# magicmouth-v0_1-ds.net
KiCad netlist of a schematic drawn in EAGLE
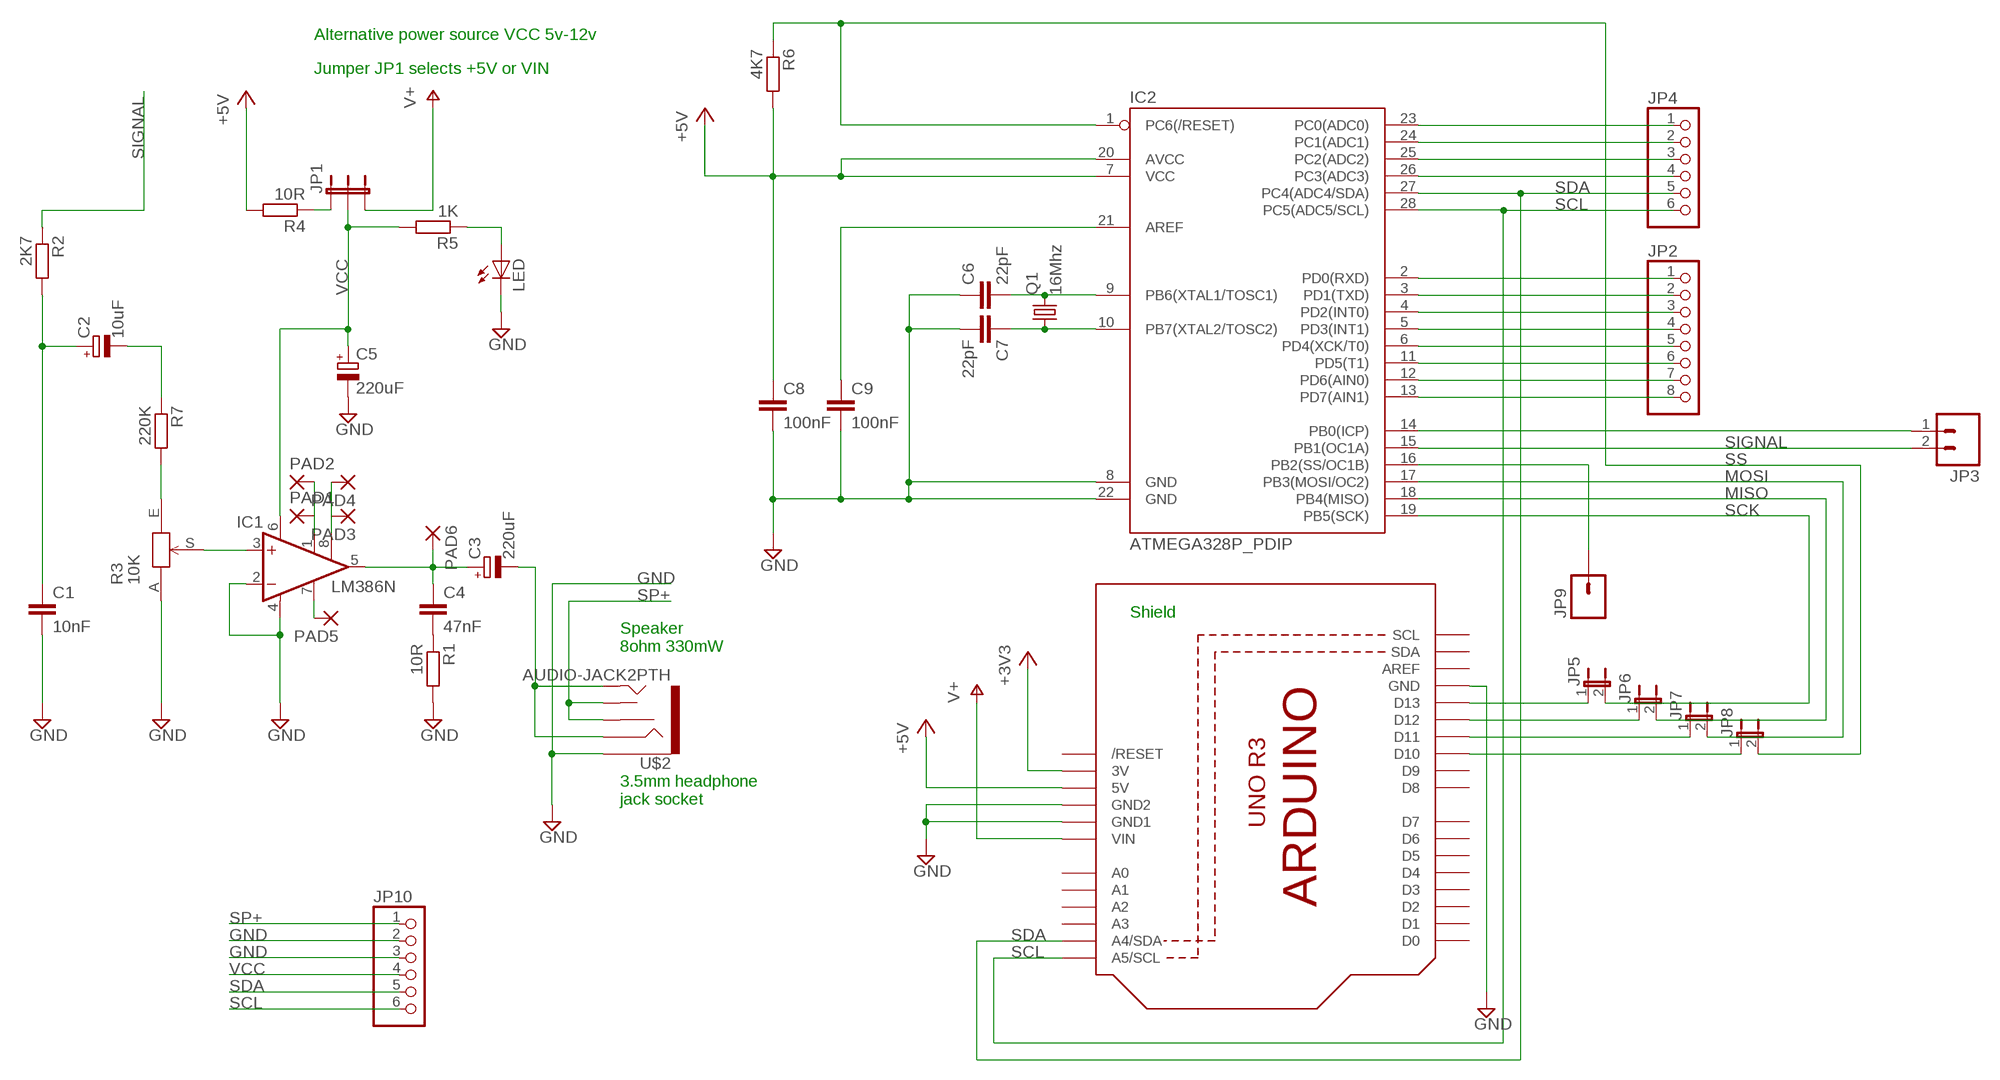
[diagram p0: schematic, sheet 1]

(export (version "E")
  (design (tool "Eeschema 10.0.6"))
  (components
    (comp (ref "C1")
      (value "10nF")
      (footprint "eagle-import:C050-025X075")
      (libsource (lib "eagle-import") (part "C-EU050-025X075"))
    )
    (comp (ref "C2")
      (value "10uF")
      (footprint "eagle-import:E2,5-7")
      (libsource (lib "eagle-import") (part "CPOL-EUE2.5-7"))
    )
    (comp (ref "C3")
      (value "220uF")
      (footprint "eagle-import:TT2D7")
      (libsource (lib "eagle-import") (part "CPOL-EUTT2D7"))
    )
    (comp (ref "C4")
      (value "47nF")
      (footprint "eagle-import:C050-025X075")
      (libsource (lib "eagle-import") (part "C-EU050-025X075"))
    )
    (comp (ref "C5")
      (value "220uF")
      (footprint "eagle-import:TT2D7")
      (libsource (lib "eagle-import") (part "CPOL-EUTT2D7"))
    )
    (comp (ref "C6")
      (value "22pF")
      (footprint "eagle-import:C025-025X050")
      (fields (field (name "CAPACITANCE") "22 pf"))
      (libsource (lib "eagle-import") (part "C-EU025-025X050"))
    )
    (comp (ref "C7")
      (value "22pF")
      (footprint "eagle-import:C025-025X050")
      (fields (field (name "CAPACITANCE") "22 pf"))
      (libsource (lib "eagle-import") (part "C-EU025-025X050"))
    )
    (comp (ref "C8")
      (value "100nF")
      (footprint "eagle-import:C025-025X050")
      (fields (field (name "CAPACITANCE") "10 nF"))
      (libsource (lib "eagle-import") (part "C-EU025-025X050"))
    )
    (comp (ref "C9")
      (value "100nF")
      (footprint "eagle-import:C025-025X050")
      (fields (field (name "CAPACITANCE") "100 nF"))
      (libsource (lib "eagle-import") (part "C-EU025-025X050"))
    )
    (comp (ref "IC1")
      (value "LM386N")
      (footprint "eagle-import:DIL08")
      (libsource (lib "eagle-import") (part "LM386?-N1"))
    )
    (comp (ref "IC2")
      (value "ATMEGA328P_PDIP")
      (footprint "eagle-import:DIL28-3")
      (libsource (lib "eagle-import") (part "ATMEGA328P_PDIP"))
    )
    (comp (ref "JP1")
      (value "JUMPER-3PTH")
      (footprint "eagle-import:1X03")
      (libsource (lib "eagle-import") (part "JUMPER-3PTH"))
    )
    (comp (ref "JP2")
      (value "PINHD-1X8CLEANBIG")
      (footprint "eagle-import:1X08-CLEANBIG")
      (libsource (lib "eagle-import") (part "PINHD-1X8CLEANBIG"))
    )
    (comp (ref "JP3")
      (value "M021X02_NO_SILK")
      (footprint "eagle-import:1X02_NO_SILK")
      (libsource (lib "eagle-import") (part "M021X02_NO_SILK"))
    )
    (comp (ref "JP4")
      (value "PINHD-1X6CB")
      (footprint "eagle-import:1X06-CLEANBIG")
      (libsource (lib "eagle-import") (part "PINHD-1X6CB"))
    )
    (comp (ref "JP5")
      (value "JUMPER-2PTH")
      (footprint "eagle-import:1X02")
      (libsource (lib "eagle-import") (part "JUMPER-2PTH"))
    )
    (comp (ref "JP6")
      (value "JUMPER-2PTH")
      (footprint "eagle-import:1X02")
      (libsource (lib "eagle-import") (part "JUMPER-2PTH"))
    )
    (comp (ref "JP7")
      (value "JUMPER-2PTH")
      (footprint "eagle-import:1X02")
      (libsource (lib "eagle-import") (part "JUMPER-2PTH"))
    )
    (comp (ref "JP8")
      (value "JUMPER-2PTH")
      (footprint "eagle-import:1X02")
      (libsource (lib "eagle-import") (part "JUMPER-2PTH"))
    )
    (comp (ref "JP9")
      (value "M01SMDNS")
      (footprint "eagle-import:1X01NS")
      (libsource (lib "eagle-import") (part "M01SMDNS"))
    )
    (comp (ref "JP10")
      (value "PINHD-1X6CB")
      (footprint "eagle-import:1X06-CLEANBIG")
      (libsource (lib "eagle-import") (part "PINHD-1X6CB"))
    )
    (comp (ref "LED")
      (value "LED3MM")
      (footprint "eagle-import:LED3MM")
      (libsource (lib "eagle-import") (part "LED3MM"))
    )
    (comp (ref "PAD1")
      (value "1,6/0,8")
      (footprint "eagle-import:1,6_0,8")
      (libsource (lib "eagle-import") (part "1,6/0,8"))
    )
    (comp (ref "PAD2")
      (value "1,6/0,8")
      (footprint "eagle-import:1,6_0,8")
      (libsource (lib "eagle-import") (part "1,6/0,8"))
    )
    (comp (ref "PAD3")
      (value "1,6/0,8")
      (footprint "eagle-import:1,6_0,8")
      (libsource (lib "eagle-import") (part "1,6/0,8"))
    )
    (comp (ref "PAD4")
      (value "1,6/0,8")
      (footprint "eagle-import:1,6_0,8")
      (libsource (lib "eagle-import") (part "1,6/0,8"))
    )
    (comp (ref "PAD5")
      (value "1,6/0,8")
      (footprint "eagle-import:1,6_0,8")
      (libsource (lib "eagle-import") (part "1,6/0,8"))
    )
    (comp (ref "PAD6")
      (value "1,6/0,8")
      (footprint "eagle-import:1,6_0,8")
      (libsource (lib "eagle-import") (part "1,6/0,8"))
    )
    (comp (ref "Q1")
      (value "16Mhz")
      (footprint "eagle-import:HC49_S")
      (libsource (lib "eagle-import") (part "CRYSTALHC49S"))
    )
    (comp (ref "R1")
      (value "10R")
      (footprint "eagle-import:0207_7")
      (libsource (lib "eagle-import") (part "resistor_R-EU_0207/7"))
    )
    (comp (ref "R2")
      (value "2K7")
      (footprint "eagle-import:0207_7")
      (libsource (lib "eagle-import") (part "R-EU_0207/7"))
    )
    (comp (ref "R3")
      (value "10K")
      (footprint "eagle-import:3352T")
      (libsource (lib "eagle-import") (part "TPOT3352"))
    )
    (comp (ref "R4")
      (value "10R")
      (footprint "eagle-import:0207_7")
      (libsource (lib "eagle-import") (part "R-EU_0207/7"))
    )
    (comp (ref "R5")
      (value "1K")
      (footprint "eagle-import:0207_7")
      (libsource (lib "eagle-import") (part "R-EU_0207/7"))
    )
    (comp (ref "R6")
      (value "4K7")
      (footprint "eagle-import:0207_7")
      (fields (field (name "RESISTANCE") "4K7"))
      (libsource (lib "eagle-import") (part "R-EU_0207/7"))
    )
    (comp (ref "R7")
      (value "220K")
      (footprint "eagle-import:0207_7")
      (libsource (lib "eagle-import") (part "resistor_R-EU_0207/7"))
    )
    (comp (ref "U$2")
      (value "AUDIO-JACK2PTH")
      (footprint "eagle-import:AUDIO-JACK")
      (libsource (lib "eagle-import") (part "AUDIO-JACK2PTH"))
    )
    (comp (ref "U1")
      (value "ARDUINOR3-NOIOREF-NOTEXT")
      (footprint "eagle-import:ARDUINOR3-NOTEXT-NOIOREF")
      (libsource (lib "eagle-import") (part "ARDUINOR3-NOIOREF-NOTEXT"))
    )
  )
  (nets
    (net (code "1") (name "+3V3") (class "Default")
      (node (ref "U1") (pin "3V") (pinfunction "3V_3V") (pintype "power_in"))
    )
    (net (code "2") (name "+5V") (class "Default")
      (node (ref "C8") (pin "1") (pinfunction "1_1") (pintype "passive"))
      (node (ref "IC2") (pin "20") (pinfunction "AVCC_20") (pintype "bidirectional"))
      (node (ref "IC2") (pin "7") (pinfunction "VCC_7") (pintype "bidirectional"))
      (node (ref "R4") (pin "2") (pinfunction "2_2") (pintype "passive"))
      (node (ref "R6") (pin "2") (pinfunction "2_2") (pintype "passive"))
      (node (ref "U1") (pin "5V") (pinfunction "5V_5V") (pintype "power_in"))
    )
    (net (code "3") (name "/MISO") (class "Default")
      (node (ref "IC2") (pin "18") (pinfunction "PB4(MISO)_18") (pintype "bidirectional"))
      (node (ref "JP6") (pin "2") (pinfunction "2_2") (pintype "passive"))
    )
    (net (code "4") (name "/MOSI") (class "Default")
      (node (ref "IC2") (pin "17") (pinfunction "PB3(MOSI/OC2)_17") (pintype "bidirectional"))
      (node (ref "JP7") (pin "2") (pinfunction "2_2") (pintype "passive"))
    )
    (net (code "5") (name "/SCK") (class "Default")
      (node (ref "IC2") (pin "19") (pinfunction "PB5(SCK)_19") (pintype "bidirectional"))
      (node (ref "JP5") (pin "2") (pinfunction "2_2") (pintype "passive"))
    )
    (net (code "6") (name "/SCL") (class "Default")
      (node (ref "IC2") (pin "28") (pinfunction "PC5(ADC5/SCL)_28") (pintype "bidirectional"))
      (node (ref "JP10") (pin "6") (pinfunction "6_6") (pintype "passive"))
      (node (ref "JP4") (pin "6") (pinfunction "6_6") (pintype "passive"))
      (node (ref "U1") (pin "A5") (pinfunction "A5/SCL_A5") (pintype "bidirectional"))
    )
    (net (code "7") (name "/SDA") (class "Default")
      (node (ref "IC2") (pin "27") (pinfunction "PC4(ADC4/SDA)_27") (pintype "bidirectional"))
      (node (ref "JP10") (pin "5") (pinfunction "5_5") (pintype "passive"))
      (node (ref "JP4") (pin "5") (pinfunction "5_5") (pintype "passive"))
      (node (ref "U1") (pin "A4") (pinfunction "A4/SDA_A4") (pintype "bidirectional"))
    )
    (net (code "8") (name "/SIGNAL") (class "Default")
      (node (ref "IC2") (pin "15") (pinfunction "PB1(OC1A)_15") (pintype "bidirectional"))
      (node (ref "JP3") (pin "2") (pinfunction "2_2") (pintype "passive"))
      (node (ref "R2") (pin "1") (pinfunction "1_1") (pintype "passive"))
    )
    (net (code "9") (name "/SP+") (class "Default")
      (node (ref "JP10") (pin "1") (pinfunction "1_1") (pintype "passive"))
      (node (ref "U$2") (pin "RSH") (pinfunction "RSH_RSH") (pintype "bidirectional"))
      (node (ref "U$2") (pin "TSH") (pinfunction "TSH_TSH") (pintype "bidirectional"))
    )
    (net (code "10") (name "/SS") (class "Default")
      (node (ref "IC2") (pin "1") (pinfunction "PC6(/RESET)_1") (pintype "bidirectional"))
      (node (ref "JP8") (pin "2") (pinfunction "2_2") (pintype "passive"))
      (node (ref "R6") (pin "1") (pinfunction "1_1") (pintype "passive"))
    )
    (net (code "11") (name "/VCC") (class "Default")
      (node (ref "C5") (pin "+") (pinfunction "+_+") (pintype "passive"))
      (node (ref "IC1") (pin "6") (pinfunction "VS_6") (pintype "power_in"))
      (node (ref "JP1") (pin "2") (pinfunction "2_2") (pintype "passive"))
      (node (ref "JP10") (pin "4") (pinfunction "4_4") (pintype "passive"))
      (node (ref "R5") (pin "2") (pinfunction "2_2") (pintype "passive"))
    )
    (net (code "12") (name "GND") (class "Default")
      (node (ref "C1") (pin "2") (pinfunction "2_2") (pintype "passive"))
      (node (ref "C5") (pin "-") (pinfunction "-_-") (pintype "passive"))
      (node (ref "C6") (pin "1") (pinfunction "1_1") (pintype "passive"))
      (node (ref "C7") (pin "2") (pinfunction "2_2") (pintype "passive"))
      (node (ref "C8") (pin "2") (pinfunction "2_2") (pintype "passive"))
      (node (ref "C9") (pin "2") (pinfunction "2_2") (pintype "passive"))
      (node (ref "IC1") (pin "2") (pinfunction "-IN_2") (pintype "input"))
      (node (ref "IC1") (pin "4") (pinfunction "GND_4") (pintype "power_in"))
      (node (ref "IC2") (pin "22") (pinfunction "GND_22") (pintype "bidirectional"))
      (node (ref "IC2") (pin "8") (pinfunction "GND_8") (pintype "bidirectional"))
      (node (ref "JP10") (pin "2") (pinfunction "2_2") (pintype "passive"))
      (node (ref "JP10") (pin "3") (pinfunction "3_3") (pintype "passive"))
      (node (ref "LED") (pin "K") (pinfunction "C_K") (pintype "passive"))
      (node (ref "R1") (pin "2") (pinfunction "2_2") (pintype "passive"))
      (node (ref "R3") (pin "A") (pinfunction "A_A") (pintype "passive"))
      (node (ref "U$2") (pin "SLEEVE") (pinfunction "SLEEVE_SLEEVE") (pintype "bidirectional"))
      (node (ref "U1") (pin "GND") (pinfunction "GND_GND") (pintype "power_in"))
      (node (ref "U1") (pin "GND1") (pinfunction "GND1_GND1") (pintype "power_in"))
      (node (ref "U1") (pin "GND2") (pinfunction "GND2_GND2") (pintype "power_in"))
    )
    (net (code "13") (name "Net-(C1-Pad1)") (class "Default")
      (node (ref "C1") (pin "1") (pinfunction "1_1") (pintype "passive"))
      (node (ref "C2") (pin "+") (pinfunction "+_+") (pintype "passive"))
      (node (ref "R2") (pin "2") (pinfunction "2_2") (pintype "passive"))
    )
    (net (code "14") (name "Net-(C2-Pad-)") (class "Default")
      (node (ref "C2") (pin "-") (pinfunction "-_-") (pintype "passive"))
      (node (ref "R7") (pin "1") (pinfunction "1_1") (pintype "passive"))
    )
    (net (code "15") (name "Net-(C3-Pad-)") (class "Default")
      (node (ref "C3") (pin "-") (pinfunction "-_-") (pintype "passive"))
      (node (ref "U$2") (pin "RING") (pinfunction "RING_RING") (pintype "bidirectional"))
      (node (ref "U$2") (pin "TIP") (pinfunction "TIP_TIP") (pintype "bidirectional"))
    )
    (net (code "16") (name "Net-(C4-Pad2)") (class "Default")
      (node (ref "C4") (pin "2") (pinfunction "2_2") (pintype "passive"))
      (node (ref "R1") (pin "1") (pinfunction "1_1") (pintype "passive"))
    )
    (net (code "17") (name "Net-(IC1-+IN)") (class "Default")
      (node (ref "IC1") (pin "3") (pinfunction "+IN_3") (pintype "input"))
      (node (ref "R3") (pin "S") (pinfunction "S_S") (pintype "passive"))
    )
    (net (code "18") (name "Net-(IC1-BYPASS)") (class "Default")
      (node (ref "IC1") (pin "7") (pinfunction "BYPASS_7") (pintype "passive"))
      (node (ref "PAD5") (pin "1") (pinfunction "P_1") (pintype "passive"))
    )
    (net (code "19") (name "Net-(IC1-OUT)") (class "Default")
      (node (ref "C3") (pin "+") (pinfunction "+_+") (pintype "passive"))
      (node (ref "C4") (pin "1") (pinfunction "1_1") (pintype "passive"))
      (node (ref "IC1") (pin "5") (pinfunction "OUT_5") (pintype "output"))
      (node (ref "PAD6") (pin "1") (pinfunction "P_1") (pintype "passive"))
    )
    (net (code "20") (name "Net-(IC2-AREF)") (class "Default")
      (node (ref "C9") (pin "1") (pinfunction "1_1") (pintype "passive"))
      (node (ref "IC2") (pin "21") (pinfunction "AREF_21") (pintype "bidirectional"))
    )
    (net (code "21") (name "Net-(IC2-PB0(ICP))") (class "Default")
      (node (ref "IC2") (pin "14") (pinfunction "PB0(ICP)_14") (pintype "bidirectional"))
      (node (ref "JP3") (pin "1") (pinfunction "1_1") (pintype "passive"))
    )
    (net (code "22") (name "Net-(IC2-PB2(SS{slash}OC1B))") (class "Default")
      (node (ref "IC2") (pin "16") (pinfunction "PB2(SS/OC1B)_16") (pintype "bidirectional"))
      (node (ref "JP9") (pin "1") (pinfunction "1_1") (pintype "passive"))
    )
    (net (code "23") (name "Net-(IC2-PB6(XTAL1{slash}TOSC1))") (class "Default")
      (node (ref "C6") (pin "2") (pinfunction "2_2") (pintype "passive"))
      (node (ref "IC2") (pin "9") (pinfunction "PB6(XTAL1/TOSC1)_9") (pintype "bidirectional"))
      (node (ref "Q1") (pin "2") (pinfunction "2_2") (pintype "passive"))
    )
    (net (code "24") (name "Net-(IC2-PB7(XTAL2{slash}TOSC2))") (class "Default")
      (node (ref "C7") (pin "1") (pinfunction "1_1") (pintype "passive"))
      (node (ref "IC2") (pin "10") (pinfunction "PB7(XTAL2/TOSC2)_10") (pintype "bidirectional"))
      (node (ref "Q1") (pin "1") (pinfunction "1_1") (pintype "passive"))
    )
    (net (code "25") (name "Net-(IC2-PC0(ADC0))") (class "Default")
      (node (ref "IC2") (pin "23") (pinfunction "PC0(ADC0)_23") (pintype "bidirectional"))
      (node (ref "JP4") (pin "1") (pinfunction "1_1") (pintype "passive"))
    )
    (net (code "26") (name "Net-(IC2-PC1(ADC1))") (class "Default")
      (node (ref "IC2") (pin "24") (pinfunction "PC1(ADC1)_24") (pintype "bidirectional"))
      (node (ref "JP4") (pin "2") (pinfunction "2_2") (pintype "passive"))
    )
    (net (code "27") (name "Net-(IC2-PC2(ADC2))") (class "Default")
      (node (ref "IC2") (pin "25") (pinfunction "PC2(ADC2)_25") (pintype "bidirectional"))
      (node (ref "JP4") (pin "3") (pinfunction "3_3") (pintype "passive"))
    )
    (net (code "28") (name "Net-(IC2-PC3(ADC3))") (class "Default")
      (node (ref "IC2") (pin "26") (pinfunction "PC3(ADC3)_26") (pintype "bidirectional"))
      (node (ref "JP4") (pin "4") (pinfunction "4_4") (pintype "passive"))
    )
    (net (code "29") (name "Net-(IC2-PD0(RXD))") (class "Default")
      (node (ref "IC2") (pin "2") (pinfunction "PD0(RXD)_2") (pintype "bidirectional"))
      (node (ref "JP2") (pin "1") (pinfunction "1_1") (pintype "passive"))
    )
    (net (code "30") (name "Net-(IC2-PD1(TXD))") (class "Default")
      (node (ref "IC2") (pin "3") (pinfunction "PD1(TXD)_3") (pintype "bidirectional"))
      (node (ref "JP2") (pin "2") (pinfunction "2_2") (pintype "passive"))
    )
    (net (code "31") (name "Net-(IC2-PD2(INT0))") (class "Default")
      (node (ref "IC2") (pin "4") (pinfunction "PD2(INT0)_4") (pintype "bidirectional"))
      (node (ref "JP2") (pin "3") (pinfunction "3_3") (pintype "passive"))
    )
    (net (code "32") (name "Net-(IC2-PD3(INT1))") (class "Default")
      (node (ref "IC2") (pin "5") (pinfunction "PD3(INT1)_5") (pintype "bidirectional"))
      (node (ref "JP2") (pin "4") (pinfunction "4_4") (pintype "passive"))
    )
    (net (code "33") (name "Net-(IC2-PD4(XCK{slash}T0))") (class "Default")
      (node (ref "IC2") (pin "6") (pinfunction "PD4(XCK/T0)_6") (pintype "bidirectional"))
      (node (ref "JP2") (pin "5") (pinfunction "5_5") (pintype "passive"))
    )
    (net (code "34") (name "Net-(IC2-PD5(T1))") (class "Default")
      (node (ref "IC2") (pin "11") (pinfunction "PD5(T1)_11") (pintype "bidirectional"))
      (node (ref "JP2") (pin "6") (pinfunction "6_6") (pintype "passive"))
    )
    (net (code "35") (name "Net-(IC2-PD6(AIN0))") (class "Default")
      (node (ref "IC2") (pin "12") (pinfunction "PD6(AIN0)_12") (pintype "bidirectional"))
      (node (ref "JP2") (pin "7") (pinfunction "7_7") (pintype "passive"))
    )
    (net (code "36") (name "Net-(IC2-PD7(AIN1))") (class "Default")
      (node (ref "IC2") (pin "13") (pinfunction "PD7(AIN1)_13") (pintype "bidirectional"))
      (node (ref "JP2") (pin "8") (pinfunction "8_8") (pintype "passive"))
    )
    (net (code "37") (name "Net-(JP1-Pad1)") (class "Default")
      (node (ref "JP1") (pin "1") (pinfunction "1_1") (pintype "passive"))
      (node (ref "R4") (pin "1") (pinfunction "1_1") (pintype "passive"))
    )
    (net (code "38") (name "Net-(JP5-Pad1)") (class "Default")
      (node (ref "JP5") (pin "1") (pinfunction "1_1") (pintype "passive"))
      (node (ref "U1") (pin "D13") (pinfunction "D13_D13") (pintype "bidirectional"))
    )
    (net (code "39") (name "Net-(JP6-Pad1)") (class "Default")
      (node (ref "JP6") (pin "1") (pinfunction "1_1") (pintype "passive"))
      (node (ref "U1") (pin "D12") (pinfunction "D12_D12") (pintype "bidirectional"))
    )
    (net (code "40") (name "Net-(JP7-Pad1)") (class "Default")
      (node (ref "JP7") (pin "1") (pinfunction "1_1") (pintype "passive"))
      (node (ref "U1") (pin "D11") (pinfunction "D11_D11") (pintype "bidirectional"))
    )
    (net (code "41") (name "Net-(JP8-Pad1)") (class "Default")
      (node (ref "JP8") (pin "1") (pinfunction "1_1") (pintype "passive"))
      (node (ref "U1") (pin "D10") (pinfunction "D10_D10") (pintype "bidirectional"))
    )
    (net (code "42") (name "Net-(LED-PadA)") (class "Default")
      (node (ref "LED") (pin "A") (pinfunction "A_A") (pintype "passive"))
      (node (ref "R5") (pin "1") (pinfunction "1_1") (pintype "passive"))
    )
    (net (code "43") (name "Net-(PAD1-P)") (class "Default")
      (node (ref "IC1") (pin "1") (pinfunction "GAIN_1") (pintype "passive"))
      (node (ref "PAD1") (pin "1") (pinfunction "P_1") (pintype "passive"))
      (node (ref "PAD2") (pin "1") (pinfunction "P_1") (pintype "passive"))
    )
    (net (code "44") (name "Net-(PAD3-P)") (class "Default")
      (node (ref "IC1") (pin "8") (pinfunction "GAIN_8") (pintype "passive"))
      (node (ref "PAD3") (pin "1") (pinfunction "P_1") (pintype "passive"))
      (node (ref "PAD4") (pin "1") (pinfunction "P_1") (pintype "passive"))
    )
    (net (code "45") (name "Net-(R3-PadE)") (class "Default")
      (node (ref "R3") (pin "E") (pinfunction "E_E") (pintype "passive"))
      (node (ref "R7") (pin "2") (pinfunction "2_2") (pintype "passive"))
    )
    (net (code "46") (name "V+") (class "Default")
      (node (ref "JP1") (pin "3") (pinfunction "3_3") (pintype "passive"))
      (node (ref "U1") (pin "VIN") (pinfunction "VIN_VIN") (pintype "power_in"))
    )
    (net (code "47") (name "unconnected-(U1-PadA0)") (class "Default")
      (node (ref "U1") (pin "A0") (pinfunction "A0_A0") (pintype "bidirectional"))
    )
    (net (code "48") (name "unconnected-(U1-PadA1)") (class "Default")
      (node (ref "U1") (pin "A1") (pinfunction "A1_A1") (pintype "bidirectional"))
    )
    (net (code "49") (name "unconnected-(U1-PadA2)") (class "Default")
      (node (ref "U1") (pin "A2") (pinfunction "A2_A2") (pintype "bidirectional"))
    )
    (net (code "50") (name "unconnected-(U1-PadA3)") (class "Default")
      (node (ref "U1") (pin "A3") (pinfunction "A3_A3") (pintype "bidirectional"))
    )
    (net (code "51") (name "unconnected-(U1-PadAREF)") (class "Default")
      (node (ref "U1") (pin "AREF") (pinfunction "AREF_AREF") (pintype "bidirectional"))
    )
    (net (code "52") (name "unconnected-(U1-PadD0)") (class "Default")
      (node (ref "U1") (pin "D0") (pinfunction "D0_D0") (pintype "bidirectional"))
    )
    (net (code "53") (name "unconnected-(U1-PadD1)") (class "Default")
      (node (ref "U1") (pin "D1") (pinfunction "D1_D1") (pintype "bidirectional"))
    )
    (net (code "54") (name "unconnected-(U1-PadD2)") (class "Default")
      (node (ref "U1") (pin "D2") (pinfunction "D2_D2") (pintype "bidirectional"))
    )
    (net (code "55") (name "unconnected-(U1-PadD3)") (class "Default")
      (node (ref "U1") (pin "D3") (pinfunction "D3_D3") (pintype "bidirectional"))
    )
    (net (code "56") (name "unconnected-(U1-PadD4)") (class "Default")
      (node (ref "U1") (pin "D4") (pinfunction "D4_D4") (pintype "bidirectional"))
    )
    (net (code "57") (name "unconnected-(U1-PadD5)") (class "Default")
      (node (ref "U1") (pin "D5") (pinfunction "D5_D5") (pintype "bidirectional"))
    )
    (net (code "58") (name "unconnected-(U1-PadD6)") (class "Default")
      (node (ref "U1") (pin "D6") (pinfunction "D6_D6") (pintype "bidirectional"))
    )
    (net (code "59") (name "unconnected-(U1-PadD7)") (class "Default")
      (node (ref "U1") (pin "D7") (pinfunction "D7_D7") (pintype "bidirectional"))
    )
    (net (code "60") (name "unconnected-(U1-PadD8)") (class "Default")
      (node (ref "U1") (pin "D8") (pinfunction "D8_D8") (pintype "bidirectional"))
    )
    (net (code "61") (name "unconnected-(U1-PadD9)") (class "Default")
      (node (ref "U1") (pin "D9") (pinfunction "D9_D9") (pintype "bidirectional"))
    )
    (net (code "62") (name "unconnected-(U1-PadSCL)") (class "Default")
      (node (ref "U1") (pin "SCL") (pinfunction "SCL_SCL") (pintype "bidirectional"))
    )
    (net (code "63") (name "unconnected-(U1-PadSDA)") (class "Default")
      (node (ref "U1") (pin "SDA") (pinfunction "SDA_SDA") (pintype "bidirectional"))
    )
    (net (code "64") (name "unconnected-(U1-{slash}RESET-PadRESET)") (class "Default")
      (node (ref "U1") (pin "RESET") (pinfunction "/RESET_RESET") (pintype "bidirectional"))
    )
  )
)
